# main.net
KiCad netlist of a schematic drawn in Altium Designer
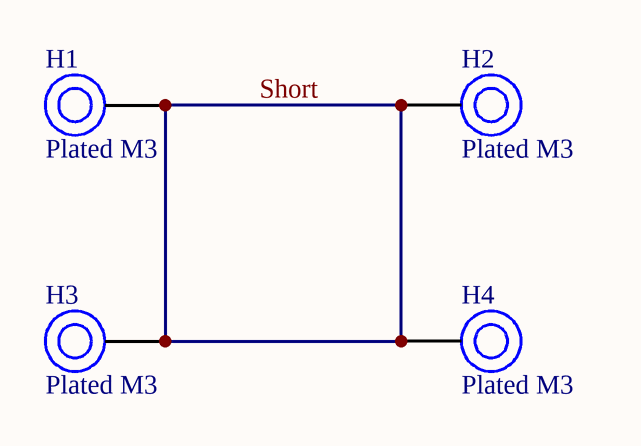
[diagram p0: main.SchDoc]

(export (version "E")
  (design (tool "Eeschema 10.0.6"))
  (components
    (comp (ref "H1")
      (value "Plated M3")
      (footprint "MountingHole_3.2mm_M3_Pad_Via_Unplated")
      (libsource (lib "jlofw") (part "Mounting_Hole"))
    )
    (comp (ref "H2")
      (value "Plated M3")
      (footprint "MountingHole_3.2mm_M3_Pad_Via_Unplated")
      (libsource (lib "jlofw") (part "Mounting_Hole"))
    )
    (comp (ref "H3")
      (value "Plated M3")
      (footprint "MountingHole_3.2mm_M3_Pad_Via_Unplated")
      (libsource (lib "jlofw") (part "Mounting_Hole"))
    )
    (comp (ref "H4")
      (value "Plated M3")
      (footprint "MountingHole_3.2mm_M3_Pad_Via_Unplated")
      (libsource (lib "jlofw") (part "Mounting_Hole"))
    )
  )
  (nets
    (net (code "1") (name "/Short") (class "Default")
      (node (ref "H1") (pin "1") (pinfunction "1_1") (pintype "passive"))
      (node (ref "H2") (pin "1") (pinfunction "1_1") (pintype "passive"))
      (node (ref "H3") (pin "1") (pinfunction "1_1") (pintype "passive"))
      (node (ref "H4") (pin "1") (pinfunction "1_1") (pintype "passive"))
    )
  )
)
